# Esquematico.net
KiCad netlist of a schematic drawn in EAGLE
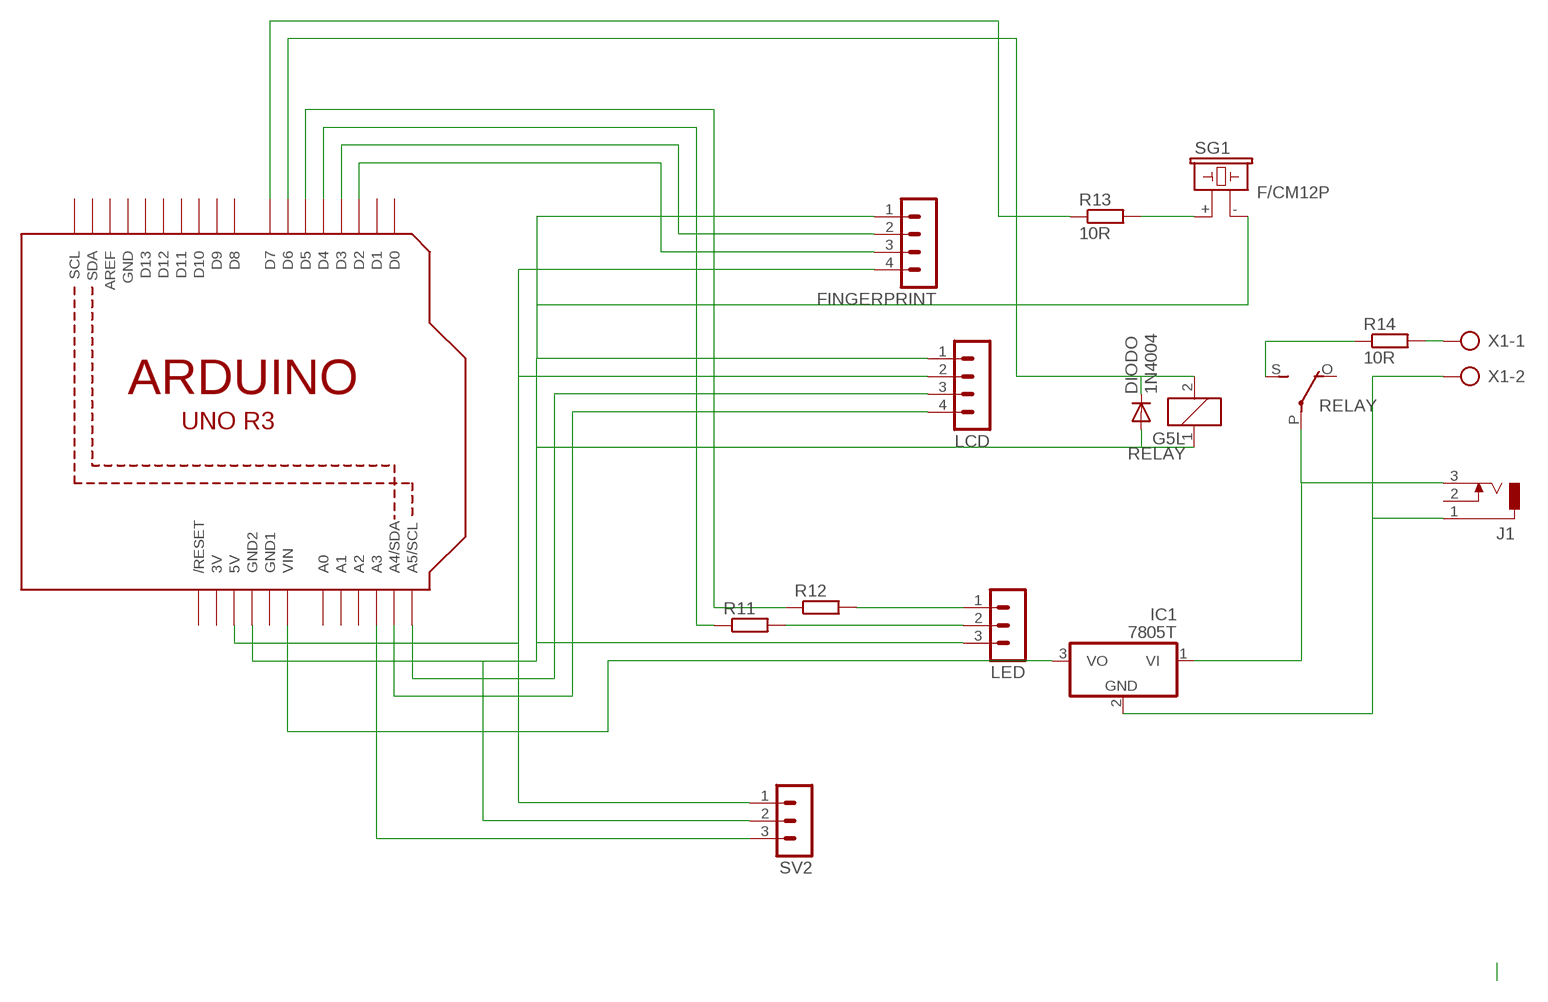
[diagram p0: schematic, sheet 1]

(export (version "E")
  (design (tool "Eeschema 10.0.6"))
  (components
    (comp (ref "DIODO")
      (value "1N4004")
      (footprint "eagle-import:DO41-10")
      (libsource (lib "eagle-import") (part "1N4004"))
    )
    (comp (ref "FINGERPRINT")
      (value "MA04-1")
      (footprint "eagle-import:MA04-1")
      (libsource (lib "eagle-import") (part "MA04-1"))
    )
    (comp (ref "IC1")
      (value "7805T")
      (footprint "eagle-import:TO220H")
      (libsource (lib "eagle-import") (part "78T05"))
    )
    (comp (ref "J1")
      (value "DCJ0303")
      (footprint "eagle-import:DCJ0303")
      (libsource (lib "eagle-import") (part "DCJ0303"))
    )
    (comp (ref "LCD")
      (value "MA04-1")
      (footprint "eagle-import:MA04-1")
      (libsource (lib "eagle-import") (part "MA04-1"))
    )
    (comp (ref "LED")
      (value "MA03-1")
      (footprint "eagle-import:MA03-1")
      (libsource (lib "eagle-import") (part "MA03-1"))
    )
    (comp (ref "Q1")
      (value "ARDUINOR3-NOIOREF-NOTEXT")
      (footprint "eagle-import:ARDUINOR3-NOTEXT-NOIOREF")
      (libsource (lib "eagle-import") (part "ARDUINOR3-NOIOREF-NOTEXT"))
    )
    (comp (ref "R11")
      (value "R-EU_0309/10")
      (footprint "eagle-import:0309_10")
      (libsource (lib "eagle-import") (part "R-EU_0309/10"))
    )
    (comp (ref "R12")
      (value "R-EU_0309/10")
      (footprint "eagle-import:0309_10")
      (libsource (lib "eagle-import") (part "R-EU_0309/10"))
    )
    (comp (ref "R13")
      (value "10R")
      (footprint "eagle-import:0309_10")
      (libsource (lib "eagle-import") (part "R-EU_0309/10"))
    )
    (comp (ref "R14")
      (value "10R")
      (footprint "eagle-import:P0817_22")
      (libsource (lib "eagle-import") (part "R-EU_0817/22"))
    )
    (comp (ref "RELAY")
      (value "G5L")
      (footprint "eagle-import:G5LE")
      (libsource (lib "eagle-import") (part "G5L"))
    )
    (comp (ref "SG1")
      (value "F/CM12P")
      (footprint "eagle-import:F_CM12P")
      (libsource (lib "eagle-import") (part "F/CM12P"))
    )
    (comp (ref "SV2")
      (value "MA03-1")
      (footprint "eagle-import:MA03-1")
      (libsource (lib "eagle-import") (part "MA03-1"))
    )
    (comp (ref "X1")
      (value "AK300/2")
      (footprint "eagle-import:AK300_2")
      (libsource (lib "eagle-import") (part "AK300/2"))
    )
  )
  (nets
    (net (code "1") (name "/3V") (class "Default")
      (node (ref "Q1") (pin "3V") (pinfunction "3V_3V") (pintype "power_in"))
    )
    (net (code "2") (name "/GND") (class "Default")
      (node (ref "Q1") (pin "GND") (pinfunction "GND_GND") (pintype "power_in"))
    )
    (net (code "3") (name "/GND1") (class "Default")
      (node (ref "Q1") (pin "GND1") (pinfunction "GND1_GND1") (pintype "power_in"))
    )
    (net (code "4") (name "Net-(DIODO-PadC)") (class "Default")
      (node (ref "DIODO") (pin "C") (pinfunction "C_C") (pintype "passive"))
      (node (ref "Q1") (pin "D6") (pinfunction "D6_D6") (pintype "bidirectional"))
      (node (ref "RELAY") (pin "2") (pinfunction "2_2") (pintype "passive"))
    )
    (net (code "5") (name "Net-(FINGERPRINT-Pad2)") (class "Default")
      (node (ref "FINGERPRINT") (pin "2") (pinfunction "2_2") (pintype "passive"))
      (node (ref "Q1") (pin "D3") (pinfunction "D3_D3") (pintype "bidirectional"))
    )
    (net (code "6") (name "Net-(FINGERPRINT-Pad3)") (class "Default")
      (node (ref "FINGERPRINT") (pin "3") (pinfunction "3_3") (pintype "passive"))
      (node (ref "Q1") (pin "D2") (pinfunction "D2_D2") (pintype "bidirectional"))
    )
    (net (code "7") (name "Net-(FINGERPRINT-Pad4)") (class "Default")
      (node (ref "FINGERPRINT") (pin "4") (pinfunction "4_4") (pintype "passive"))
      (node (ref "LCD") (pin "2") (pinfunction "2_2") (pintype "passive"))
      (node (ref "Q1") (pin "5V") (pinfunction "5V_5V") (pintype "power_in"))
      (node (ref "SV2") (pin "1") (pinfunction "1_1") (pintype "passive"))
    )
    (net (code "8") (name "Net-(IC1-GND)") (class "Default")
      (node (ref "IC1") (pin "2") (pinfunction "GND_2") (pintype "passive"))
      (node (ref "J1") (pin "1") (pinfunction "1_1") (pintype "passive"))
      (node (ref "X1") (pin "2") (pinfunction "KL_2") (pintype "passive"))
    )
    (net (code "9") (name "Net-(IC1-VI)") (class "Default")
      (node (ref "IC1") (pin "1") (pinfunction "VI_1") (pintype "input"))
      (node (ref "J1") (pin "3") (pinfunction "3_3") (pintype "passive"))
      (node (ref "RELAY") (pin "P") (pinfunction "P_P") (pintype "passive"))
    )
    (net (code "10") (name "Net-(IC1-VO)") (class "Default")
      (node (ref "IC1") (pin "3") (pinfunction "VO_3") (pintype "passive"))
      (node (ref "Q1") (pin "VIN") (pinfunction "VIN_VIN") (pintype "power_in"))
    )
    (net (code "11") (name "Net-(LED-Pad1)") (class "Default")
      (node (ref "LED") (pin "1") (pinfunction "1_1") (pintype "passive"))
      (node (ref "R12") (pin "2") (pinfunction "2_2") (pintype "passive"))
    )
    (net (code "12") (name "Net-(LED-Pad2)") (class "Default")
      (node (ref "LED") (pin "2") (pinfunction "2_2") (pintype "passive"))
      (node (ref "R11") (pin "2") (pinfunction "2_2") (pintype "passive"))
    )
    (net (code "13") (name "Net-(Q1-A4{slash}SDA)") (class "Default")
      (node (ref "LCD") (pin "4") (pinfunction "4_4") (pintype "passive"))
      (node (ref "Q1") (pin "A4") (pinfunction "A4/SDA_A4") (pintype "bidirectional"))
    )
    (net (code "14") (name "Net-(Q1-A5{slash}SCL)") (class "Default")
      (node (ref "LCD") (pin "3") (pinfunction "3_3") (pintype "passive"))
      (node (ref "Q1") (pin "A5") (pinfunction "A5/SCL_A5") (pintype "bidirectional"))
    )
    (net (code "15") (name "Net-(Q1-PadA3)") (class "Default")
      (node (ref "Q1") (pin "A3") (pinfunction "A3_A3") (pintype "bidirectional"))
      (node (ref "SV2") (pin "3") (pinfunction "3_3") (pintype "passive"))
    )
    (net (code "16") (name "Net-(Q1-PadD4)") (class "Default")
      (node (ref "Q1") (pin "D4") (pinfunction "D4_D4") (pintype "bidirectional"))
      (node (ref "R11") (pin "1") (pinfunction "1_1") (pintype "passive"))
    )
    (net (code "17") (name "Net-(Q1-PadD5)") (class "Default")
      (node (ref "Q1") (pin "D5") (pinfunction "D5_D5") (pintype "bidirectional"))
      (node (ref "R12") (pin "1") (pinfunction "1_1") (pintype "passive"))
    )
    (net (code "18") (name "Net-(Q1-PadD7)") (class "Default")
      (node (ref "Q1") (pin "D7") (pinfunction "D7_D7") (pintype "bidirectional"))
      (node (ref "R13") (pin "1") (pinfunction "1_1") (pintype "passive"))
    )
    (net (code "19") (name "Net-(R14-Pad1)") (class "Default")
      (node (ref "R14") (pin "1") (pinfunction "1_1") (pintype "passive"))
      (node (ref "RELAY") (pin "S") (pinfunction "S_S") (pintype "passive"))
    )
    (net (code "20") (name "Net-(SG1-1)") (class "Default")
      (node (ref "R13") (pin "2") (pinfunction "2_2") (pintype "passive"))
      (node (ref "SG1") (pin "+") (pinfunction "1_+") (pintype "passive"))
    )
    (net (code "21") (name "Net-(SG1-2)") (class "Default")
      (node (ref "DIODO") (pin "A") (pinfunction "A_A") (pintype "passive"))
      (node (ref "FINGERPRINT") (pin "1") (pinfunction "1_1") (pintype "passive"))
      (node (ref "LCD") (pin "1") (pinfunction "1_1") (pintype "passive"))
      (node (ref "LED") (pin "3") (pinfunction "3_3") (pintype "passive"))
      (node (ref "Q1") (pin "GND2") (pinfunction "GND2_GND2") (pintype "power_in"))
      (node (ref "RELAY") (pin "1") (pinfunction "1_1") (pintype "passive"))
      (node (ref "SG1") (pin "-") (pinfunction "2_-") (pintype "passive"))
      (node (ref "SV2") (pin "2") (pinfunction "2_2") (pintype "passive"))
    )
    (net (code "22") (name "Net-(X1A-KL)") (class "Default")
      (node (ref "R14") (pin "2") (pinfunction "2_2") (pintype "passive"))
      (node (ref "X1") (pin "1") (pinfunction "KL_1") (pintype "passive"))
    )
    (net (code "23") (name "unconnected-(J1-Pad2)") (class "Default")
      (node (ref "J1") (pin "2") (pinfunction "2_2") (pintype "passive"))
    )
    (net (code "24") (name "unconnected-(Q1-PadA0)") (class "Default")
      (node (ref "Q1") (pin "A0") (pinfunction "A0_A0") (pintype "bidirectional"))
    )
    (net (code "25") (name "unconnected-(Q1-PadA1)") (class "Default")
      (node (ref "Q1") (pin "A1") (pinfunction "A1_A1") (pintype "bidirectional"))
    )
    (net (code "26") (name "unconnected-(Q1-PadA2)") (class "Default")
      (node (ref "Q1") (pin "A2") (pinfunction "A2_A2") (pintype "bidirectional"))
    )
    (net (code "27") (name "unconnected-(Q1-PadAREF)") (class "Default")
      (node (ref "Q1") (pin "AREF") (pinfunction "AREF_AREF") (pintype "bidirectional"))
    )
    (net (code "28") (name "unconnected-(Q1-PadD0)") (class "Default")
      (node (ref "Q1") (pin "D0") (pinfunction "D0_D0") (pintype "bidirectional"))
    )
    (net (code "29") (name "unconnected-(Q1-PadD1)") (class "Default")
      (node (ref "Q1") (pin "D1") (pinfunction "D1_D1") (pintype "bidirectional"))
    )
    (net (code "30") (name "unconnected-(Q1-PadD8)") (class "Default")
      (node (ref "Q1") (pin "D8") (pinfunction "D8_D8") (pintype "bidirectional"))
    )
    (net (code "31") (name "unconnected-(Q1-PadD9)") (class "Default")
      (node (ref "Q1") (pin "D9") (pinfunction "D9_D9") (pintype "bidirectional"))
    )
    (net (code "32") (name "unconnected-(Q1-PadD10)") (class "Default")
      (node (ref "Q1") (pin "D10") (pinfunction "D10_D10") (pintype "bidirectional"))
    )
    (net (code "33") (name "unconnected-(Q1-PadD11)") (class "Default")
      (node (ref "Q1") (pin "D11") (pinfunction "D11_D11") (pintype "bidirectional"))
    )
    (net (code "34") (name "unconnected-(Q1-PadD12)") (class "Default")
      (node (ref "Q1") (pin "D12") (pinfunction "D12_D12") (pintype "bidirectional"))
    )
    (net (code "35") (name "unconnected-(Q1-PadD13)") (class "Default")
      (node (ref "Q1") (pin "D13") (pinfunction "D13_D13") (pintype "bidirectional"))
    )
    (net (code "36") (name "unconnected-(Q1-PadSCL)") (class "Default")
      (node (ref "Q1") (pin "SCL") (pinfunction "SCL_SCL") (pintype "bidirectional"))
    )
    (net (code "37") (name "unconnected-(Q1-PadSDA)") (class "Default")
      (node (ref "Q1") (pin "SDA") (pinfunction "SDA_SDA") (pintype "bidirectional"))
    )
    (net (code "38") (name "unconnected-(Q1-{slash}RESET-PadRESET)") (class "Default")
      (node (ref "Q1") (pin "RESET") (pinfunction "/RESET_RESET") (pintype "bidirectional"))
    )
    (net (code "39") (name "unconnected-(RELAY-PadO)") (class "Default")
      (node (ref "RELAY") (pin "O") (pinfunction "O_O") (pintype "passive"))
    )
  )
)
